# DosTres_v3.net
KiCad netlist of a schematic drawn in EAGLE
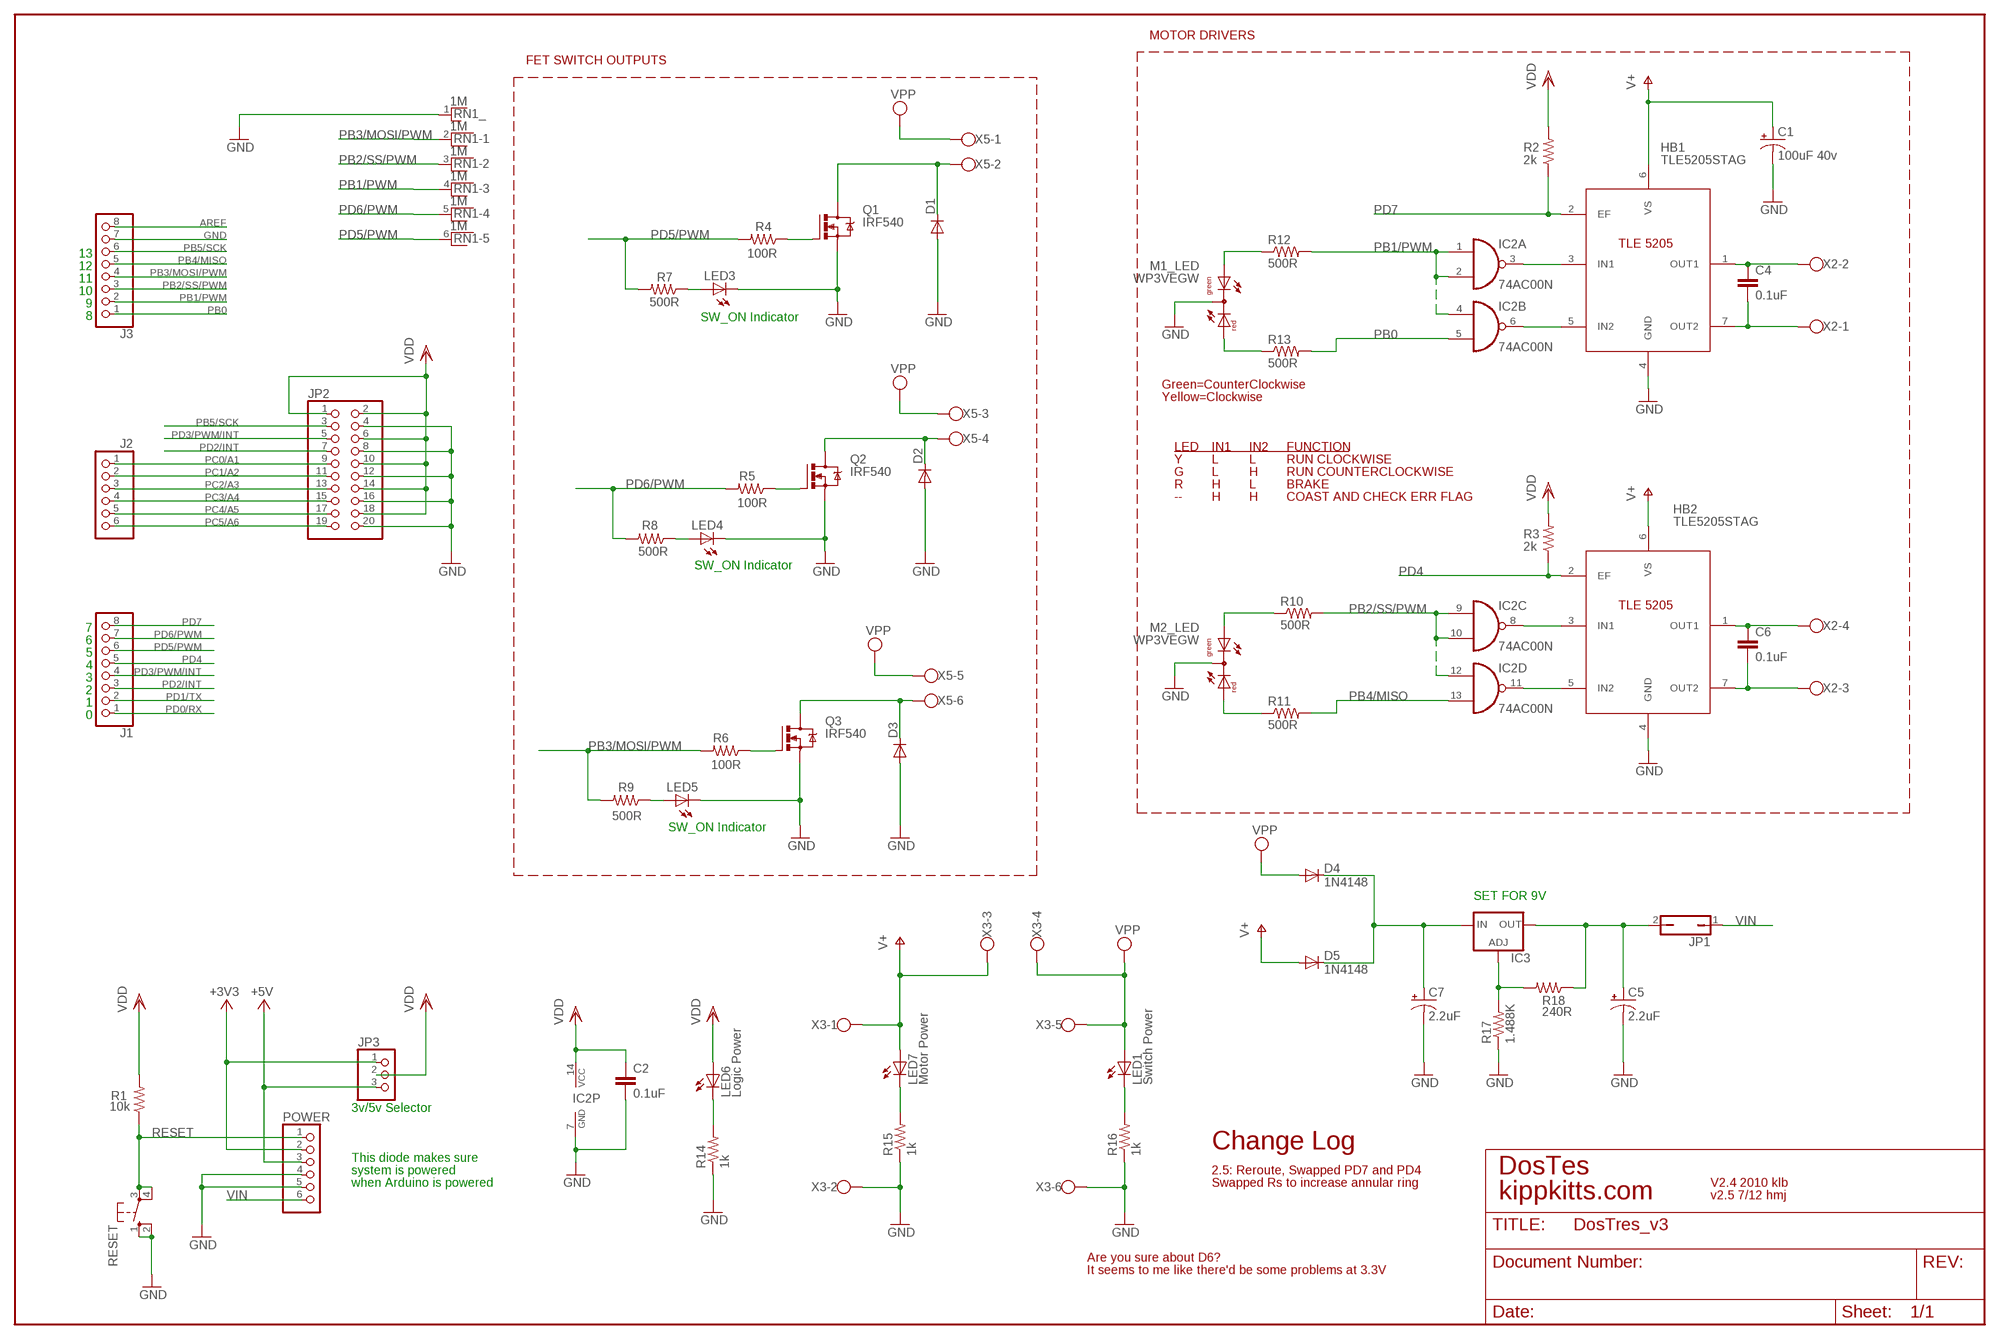
[diagram p0: schematic, sheet 1]

(export (version "E")
  (design (tool "Eeschema 10.0.6"))
  (components
    (comp (ref "C1")
      (value "100uF 40v")
      (footprint "eagle-import:E2,5-6E")
      (libsource (lib "eagle-import") (part "CPOL-USE2,5-6E"))
    )
    (comp (ref "C2")
      (value "0.1uF")
      (footprint "eagle-import:CAP-PTH-SMALL-KIT")
      (libsource (lib "eagle-import") (part "CAPKIT"))
    )
    (comp (ref "C4")
      (value "0.1uF")
      (footprint "eagle-import:CAP-PTH-SMALL-KIT")
      (libsource (lib "eagle-import") (part "CAPKIT"))
    )
    (comp (ref "C5")
      (value "2.2uF")
      (footprint "eagle-import:CPOL-RADIAL-10UF-25V")
      (libsource (lib "eagle-import") (part "CAP_POLPTH2"))
    )
    (comp (ref "C6")
      (value "0.1uF")
      (footprint "eagle-import:CAP-PTH-SMALL-KIT")
      (libsource (lib "eagle-import") (part "CAPKIT"))
    )
    (comp (ref "C7")
      (value "2.2uF")
      (footprint "eagle-import:CPOL-RADIAL-10UF-25V")
      (libsource (lib "eagle-import") (part "CAP_POLPTH2"))
    )
    (comp (ref "D1")
      (value "DIODE-1MMHOLED-7.5BH")
      (footprint "eagle-import:D-7.5BH")
      (libsource (lib "eagle-import") (part "DIODE-1MMHOLED-7.5BH"))
    )
    (comp (ref "D2")
      (value "DIODE-1MMHOLED-7.5BH")
      (footprint "eagle-import:D-7.5BH")
      (libsource (lib "eagle-import") (part "DIODE-1MMHOLED-7.5BH"))
    )
    (comp (ref "D3")
      (value "DIODE-1MMHOLED-7.5BH")
      (footprint "eagle-import:D-7.5BH")
      (libsource (lib "eagle-import") (part "DIODE-1MMHOLED-7.5BH"))
    )
    (comp (ref "D4")
      (value "1N4148")
      (footprint "eagle-import:D-7.5BH")
      (libsource (lib "eagle-import") (part "DIODE-1MMHOLED-7.5BH"))
    )
    (comp (ref "D5")
      (value "1N4148")
      (footprint "eagle-import:D-7.5BH")
      (libsource (lib "eagle-import") (part "DIODE-1MMHOLED-7.5BH"))
    )
    (comp (ref "HB1")
      (value "TLE5205STAG")
      (footprint "eagle-import:TO220-7-11")
      (libsource (lib "eagle-import") (part "TLE5205STAG"))
    )
    (comp (ref "HB2")
      (value "TLE5205STAG")
      (footprint "eagle-import:TO220-7-11")
      (libsource (lib "eagle-import") (part "TLE5205STAG"))
    )
    (comp (ref "IC2")
      (value "74AC00N")
      (footprint "eagle-import:DIL14")
      (libsource (lib "eagle-import") (part "7400NAC"))
    )
    (comp (ref "IC3")
      (value "LM317TS")
      (footprint "eagle-import:317TS")
      (libsource (lib "eagle-import") (part "LM317TS"))
    )
    (comp (ref "J1")
      (value "PINHD-1X8")
      (footprint "eagle-import:1X08")
      (libsource (lib "eagle-import") (part "PINHD-1X8"))
    )
    (comp (ref "J2")
      (value "PINHD-1X6")
      (footprint "eagle-import:1X06")
      (libsource (lib "eagle-import") (part "PINHD-1X6"))
    )
    (comp (ref "J3")
      (value "PINHD-1X8")
      (footprint "eagle-import:1X08")
      (libsource (lib "eagle-import") (part "PINHD-1X8"))
    )
    (comp (ref "JP1")
      (value "JP1Q")
      (footprint "eagle-import:JP1")
      (libsource (lib "eagle-import") (part "JP1Q"))
    )
    (comp (ref "JP2")
      (value "PINHD-2X10HAND")
      (footprint "eagle-import:2X10HAND")
      (libsource (lib "eagle-import") (part "PINHD-2X10HAND"))
    )
    (comp (ref "JP3")
      (value "PINHD-1X3")
      (footprint "eagle-import:1X03")
      (libsource (lib "eagle-import") (part "PINHD-1X3"))
    )
    (comp (ref "LED1")
      (value "Switch Power")
      (footprint "eagle-import:LED3MM")
      (libsource (lib "eagle-import") (part "LED3MMX1MM3MM"))
    )
    (comp (ref "LED3")
      (value "LED3MMX1MM3MM")
      (footprint "eagle-import:LED3MM")
      (libsource (lib "eagle-import") (part "LED3MMX1MM3MM"))
    )
    (comp (ref "LED4")
      (value "LED3MMX1MM3MM")
      (footprint "eagle-import:LED3MM")
      (libsource (lib "eagle-import") (part "LED3MMX1MM3MM"))
    )
    (comp (ref "LED5")
      (value "LED3MMX1MM3MM")
      (footprint "eagle-import:LED3MM")
      (libsource (lib "eagle-import") (part "LED3MMX1MM3MM"))
    )
    (comp (ref "LED6")
      (value "Logic Power")
      (footprint "eagle-import:LED3MM")
      (libsource (lib "eagle-import") (part "LED3MMX1MM3MM"))
    )
    (comp (ref "LED7")
      (value "Motor Power")
      (footprint "eagle-import:LED3MM")
      (libsource (lib "eagle-import") (part "LED3MMX1MM3MM"))
    )
    (comp (ref "M1_LED")
      (value "WP3VEGW")
      (footprint "eagle-import:DUOLED-A-3MM")
      (libsource (lib "eagle-import") (part "WP3VEGW"))
    )
    (comp (ref "M2_LED")
      (value "WP3VEGW")
      (footprint "eagle-import:DUOLED-A-3MM")
      (libsource (lib "eagle-import") (part "WP3VEGW"))
    )
    (comp (ref "POWER")
      (value "PINHD-1X6")
      (footprint "eagle-import:1X06")
      (libsource (lib "eagle-import") (part "PINHD-1X6"))
    )
    (comp (ref "Q1")
      (value "IRF540")
      (footprint "eagle-import:TO220BV")
      (libsource (lib "eagle-import") (part "IRF540"))
    )
    (comp (ref "Q2")
      (value "IRF540")
      (footprint "eagle-import:TO220BV")
      (libsource (lib "eagle-import") (part "IRF540"))
    )
    (comp (ref "Q3")
      (value "IRF540")
      (footprint "eagle-import:TO220BV")
      (libsource (lib "eagle-import") (part "IRF540"))
    )
    (comp (ref "R1")
      (value "10k")
      (footprint "eagle-import:0207_2V")
      (libsource (lib "eagle-import") (part "R-US_0207/2V"))
    )
    (comp (ref "R2")
      (value "2k")
      (footprint "eagle-import:0207_2V")
      (libsource (lib "eagle-import") (part "R-US_0207/2V"))
    )
    (comp (ref "R3")
      (value "2k")
      (footprint "eagle-import:0207_2V")
      (libsource (lib "eagle-import") (part "R-US_0207/2V"))
    )
    (comp (ref "R4")
      (value "100R")
      (footprint "eagle-import:0207_2V")
      (libsource (lib "eagle-import") (part "R-US_0207/2V"))
    )
    (comp (ref "R5")
      (value "100R")
      (footprint "eagle-import:0207_2V")
      (libsource (lib "eagle-import") (part "R-US_0207/2V"))
    )
    (comp (ref "R6")
      (value "100R")
      (footprint "eagle-import:0207_2V")
      (libsource (lib "eagle-import") (part "R-US_0207/2V"))
    )
    (comp (ref "R7")
      (value "500R")
      (footprint "eagle-import:0207_2V")
      (libsource (lib "eagle-import") (part "R-US_0207/2V"))
    )
    (comp (ref "R8")
      (value "500R")
      (footprint "eagle-import:0207_2V")
      (libsource (lib "eagle-import") (part "R-US_0207/2V"))
    )
    (comp (ref "R9")
      (value "500R")
      (footprint "eagle-import:0207_2V")
      (libsource (lib "eagle-import") (part "R-US_0207/2V"))
    )
    (comp (ref "R10")
      (value "500R")
      (footprint "eagle-import:0207_2V")
      (libsource (lib "eagle-import") (part "R-US_0207/2V"))
    )
    (comp (ref "R11")
      (value "500R")
      (footprint "eagle-import:0207_2V")
      (libsource (lib "eagle-import") (part "R-US_0207/2V"))
    )
    (comp (ref "R12")
      (value "500R")
      (footprint "eagle-import:0207_2V")
      (libsource (lib "eagle-import") (part "R-US_0207/2V"))
    )
    (comp (ref "R13")
      (value "500R")
      (footprint "eagle-import:0207_2V")
      (libsource (lib "eagle-import") (part "R-US_0207/2V"))
    )
    (comp (ref "R14")
      (value "1k")
      (footprint "eagle-import:0207_2V")
      (libsource (lib "eagle-import") (part "R-US_0207/2V"))
    )
    (comp (ref "R15")
      (value "1k")
      (footprint "eagle-import:0207_2V")
      (libsource (lib "eagle-import") (part "R-US_0207/2V"))
    )
    (comp (ref "R16")
      (value "1k")
      (footprint "eagle-import:0207_2V")
      (libsource (lib "eagle-import") (part "R-US_0207/2V"))
    )
    (comp (ref "R17")
      (value "1.488K")
      (footprint "eagle-import:0207_2V")
      (libsource (lib "eagle-import") (part "R-US_0207/2V"))
    )
    (comp (ref "R18")
      (value "240R")
      (footprint "eagle-import:0207_2V")
      (libsource (lib "eagle-import") (part "R-US_0207/2V"))
    )
    (comp (ref "RESET")
      (value "10-XX")
      (footprint "eagle-import:B3F-10XX")
      (fields (field (name "MPN") "B3F-1000"))
      (libsource (lib "eagle-import") (part "10-XX"))
    )
    (comp (ref "RN1")
      (value "1M")
      (footprint "eagle-import:RN-6")
      (libsource (lib "eagle-import") (part "RNX5"))
    )
    (comp (ref "X2")
      (value "W237-4")
      (footprint "eagle-import:W237-4")
      (libsource (lib "eagle-import") (part "W237-4"))
    )
    (comp (ref "X3")
      (value "W237-6")
      (footprint "eagle-import:W237-6")
      (libsource (lib "eagle-import") (part "W237-6"))
    )
    (comp (ref "X5")
      (value "W237-6")
      (footprint "eagle-import:W237-6")
      (libsource (lib "eagle-import") (part "W237-6"))
    )
  )
  (nets
    (net (code "1") (name "+3V3") (class "Default")
      (node (ref "JP3") (pin "1") (pinfunction "1_1") (pintype "passive"))
      (node (ref "POWER") (pin "2") (pinfunction "2_2") (pintype "passive"))
    )
    (net (code "2") (name "+5V") (class "Default")
      (node (ref "JP3") (pin "3") (pinfunction "3_3") (pintype "passive"))
      (node (ref "POWER") (pin "3") (pinfunction "3_3") (pintype "passive"))
    )
    (net (code "3") (name "/AREF") (class "Default")
      (node (ref "J3") (pin "8") (pinfunction "8_8") (pintype "passive"))
    )
    (net (code "4") (name "/PB0") (class "Default")
      (node (ref "IC2") (pin "5") (pinfunction "I1_5") (pintype "input"))
      (node (ref "J3") (pin "1") (pinfunction "1_1") (pintype "passive"))
      (node (ref "R13") (pin "2") (pinfunction "2_2") (pintype "passive"))
    )
    (net (code "5") (name "/PB1{slash}PWM") (class "Default")
      (node (ref "IC2") (pin "1") (pinfunction "I0_1") (pintype "input"))
      (node (ref "IC2") (pin "2") (pinfunction "I1_2") (pintype "input"))
      (node (ref "IC2") (pin "4") (pinfunction "I0_4") (pintype "input"))
      (node (ref "J3") (pin "2") (pinfunction "2_2") (pintype "passive"))
      (node (ref "R12") (pin "2") (pinfunction "2_2") (pintype "passive"))
      (node (ref "RN1") (pin "4") (pinfunction "1_4") (pintype "passive"))
    )
    (net (code "6") (name "/PB2{slash}SS{slash}PWM") (class "Default")
      (node (ref "IC2") (pin "10") (pinfunction "I1_10") (pintype "input"))
      (node (ref "IC2") (pin "12") (pinfunction "I0_12") (pintype "input"))
      (node (ref "IC2") (pin "9") (pinfunction "I0_9") (pintype "input"))
      (node (ref "J3") (pin "3") (pinfunction "3_3") (pintype "passive"))
      (node (ref "R10") (pin "2") (pinfunction "2_2") (pintype "passive"))
      (node (ref "RN1") (pin "3") (pinfunction "1_3") (pintype "passive"))
    )
    (net (code "7") (name "/PB3{slash}MOSI{slash}PWM") (class "Default")
      (node (ref "J3") (pin "4") (pinfunction "4_4") (pintype "passive"))
      (node (ref "R6") (pin "2") (pinfunction "2_2") (pintype "passive"))
      (node (ref "R9") (pin "2") (pinfunction "2_2") (pintype "passive"))
      (node (ref "RN1") (pin "2") (pinfunction "1_2") (pintype "passive"))
    )
    (net (code "8") (name "/PB4{slash}MISO") (class "Default")
      (node (ref "IC2") (pin "13") (pinfunction "I1_13") (pintype "input"))
      (node (ref "J3") (pin "5") (pinfunction "5_5") (pintype "passive"))
      (node (ref "R11") (pin "2") (pinfunction "2_2") (pintype "passive"))
    )
    (net (code "9") (name "/PB5{slash}SCK") (class "Default")
      (node (ref "J3") (pin "6") (pinfunction "6_6") (pintype "passive"))
      (node (ref "JP2") (pin "3") (pinfunction "3_3") (pintype "passive"))
    )
    (net (code "10") (name "/PC0{slash}A1") (class "Default")
      (node (ref "J2") (pin "1") (pinfunction "1_1") (pintype "passive"))
      (node (ref "JP2") (pin "9") (pinfunction "9_9") (pintype "passive"))
    )
    (net (code "11") (name "/PC1{slash}A2") (class "Default")
      (node (ref "J2") (pin "2") (pinfunction "2_2") (pintype "passive"))
      (node (ref "JP2") (pin "11") (pinfunction "11_11") (pintype "passive"))
    )
    (net (code "12") (name "/PC2{slash}A3") (class "Default")
      (node (ref "J2") (pin "3") (pinfunction "3_3") (pintype "passive"))
      (node (ref "JP2") (pin "13") (pinfunction "13_13") (pintype "passive"))
    )
    (net (code "13") (name "/PC3{slash}A4") (class "Default")
      (node (ref "J2") (pin "4") (pinfunction "4_4") (pintype "passive"))
      (node (ref "JP2") (pin "15") (pinfunction "15_15") (pintype "passive"))
    )
    (net (code "14") (name "/PC4{slash}A5") (class "Default")
      (node (ref "J2") (pin "5") (pinfunction "5_5") (pintype "passive"))
      (node (ref "JP2") (pin "17") (pinfunction "17_17") (pintype "passive"))
    )
    (net (code "15") (name "/PC5{slash}A6") (class "Default")
      (node (ref "J2") (pin "6") (pinfunction "6_6") (pintype "passive"))
      (node (ref "JP2") (pin "19") (pinfunction "19_19") (pintype "passive"))
    )
    (net (code "16") (name "/PD0{slash}RX") (class "Default")
      (node (ref "J1") (pin "1") (pinfunction "1_1") (pintype "passive"))
    )
    (net (code "17") (name "/PD1{slash}TX") (class "Default")
      (node (ref "J1") (pin "2") (pinfunction "2_2") (pintype "passive"))
    )
    (net (code "18") (name "/PD2{slash}INT") (class "Default")
      (node (ref "J1") (pin "3") (pinfunction "3_3") (pintype "passive"))
      (node (ref "JP2") (pin "7") (pinfunction "7_7") (pintype "passive"))
    )
    (net (code "19") (name "/PD3{slash}PWM{slash}INT") (class "Default")
      (node (ref "J1") (pin "4") (pinfunction "4_4") (pintype "passive"))
      (node (ref "JP2") (pin "5") (pinfunction "5_5") (pintype "passive"))
    )
    (net (code "20") (name "/PD4") (class "Default")
      (node (ref "HB2") (pin "2") (pinfunction "EF_2") (pintype "output"))
      (node (ref "J1") (pin "5") (pinfunction "5_5") (pintype "passive"))
      (node (ref "R3") (pin "1") (pinfunction "1_1") (pintype "passive"))
    )
    (net (code "21") (name "/PD5{slash}PWM") (class "Default")
      (node (ref "J1") (pin "6") (pinfunction "6_6") (pintype "passive"))
      (node (ref "R4") (pin "2") (pinfunction "2_2") (pintype "passive"))
      (node (ref "R7") (pin "2") (pinfunction "2_2") (pintype "passive"))
      (node (ref "RN1") (pin "6") (pinfunction "1_6") (pintype "passive"))
    )
    (net (code "22") (name "/PD6{slash}PWM") (class "Default")
      (node (ref "J1") (pin "7") (pinfunction "7_7") (pintype "passive"))
      (node (ref "R5") (pin "2") (pinfunction "2_2") (pintype "passive"))
      (node (ref "R8") (pin "2") (pinfunction "2_2") (pintype "passive"))
      (node (ref "RN1") (pin "5") (pinfunction "1_5") (pintype "passive"))
    )
    (net (code "23") (name "/PD7") (class "Default")
      (node (ref "HB1") (pin "2") (pinfunction "EF_2") (pintype "output"))
      (node (ref "J1") (pin "8") (pinfunction "8_8") (pintype "passive"))
      (node (ref "R2") (pin "1") (pinfunction "1_1") (pintype "passive"))
    )
    (net (code "24") (name "/RESET") (class "Default")
      (node (ref "POWER") (pin "1") (pinfunction "1_1") (pintype "passive"))
      (node (ref "R1") (pin "1") (pinfunction "1_1") (pintype "passive"))
      (node (ref "RESET") (pin "3") (pinfunction "P_3") (pintype "passive"))
      (node (ref "RESET") (pin "4") (pinfunction "P1_4") (pintype "passive"))
    )
    (net (code "25") (name "/VIN") (class "Default")
      (node (ref "JP1") (pin "1") (pinfunction "1_1") (pintype "passive"))
      (node (ref "POWER") (pin "6") (pinfunction "6_6") (pintype "passive"))
    )
    (net (code "26") (name "GND") (class "Default")
      (node (ref "C1") (pin "-") (pinfunction "-_-") (pintype "passive"))
      (node (ref "C2") (pin "2") (pinfunction "2_2") (pintype "passive"))
      (node (ref "C5") (pin "2") (pinfunction "-_2") (pintype "passive"))
      (node (ref "C7") (pin "2") (pinfunction "-_2") (pintype "passive"))
      (node (ref "D1") (pin "A") (pinfunction "A_A") (pintype "passive"))
      (node (ref "D2") (pin "A") (pinfunction "A_A") (pintype "passive"))
      (node (ref "D3") (pin "A") (pinfunction "A_A") (pintype "passive"))
      (node (ref "HB1") (pin "4") (pinfunction "GND_4") (pintype "power_in"))
      (node (ref "HB2") (pin "4") (pinfunction "GND_4") (pintype "power_in"))
      (node (ref "IC2") (pin "7") (pinfunction "GND_7") (pintype "power_in"))
      (node (ref "J3") (pin "7") (pinfunction "7_7") (pintype "passive"))
      (node (ref "JP2") (pin "12") (pinfunction "12_12") (pintype "passive"))
      (node (ref "JP2") (pin "16") (pinfunction "16_16") (pintype "passive"))
      (node (ref "JP2") (pin "20") (pinfunction "20_20") (pintype "passive"))
      (node (ref "JP2") (pin "4") (pinfunction "4_4") (pintype "passive"))
      (node (ref "JP2") (pin "8") (pinfunction "8_8") (pintype "passive"))
      (node (ref "LED3") (pin "K") (pinfunction "C_K") (pintype "passive"))
      (node (ref "LED4") (pin "K") (pinfunction "C_K") (pintype "passive"))
      (node (ref "LED5") (pin "K") (pinfunction "C_K") (pintype "passive"))
      (node (ref "M1_LED") (pin "2") (pinfunction "C_2") (pintype "passive"))
      (node (ref "M2_LED") (pin "2") (pinfunction "C_2") (pintype "passive"))
      (node (ref "POWER") (pin "4") (pinfunction "4_4") (pintype "passive"))
      (node (ref "POWER") (pin "5") (pinfunction "5_5") (pintype "passive"))
      (node (ref "Q1") (pin "S") (pinfunction "S_S") (pintype "passive"))
      (node (ref "Q2") (pin "S") (pinfunction "S_S") (pintype "passive"))
      (node (ref "Q3") (pin "S") (pinfunction "S_S") (pintype "passive"))
      (node (ref "R14") (pin "1") (pinfunction "1_1") (pintype "passive"))
      (node (ref "R15") (pin "1") (pinfunction "1_1") (pintype "passive"))
      (node (ref "R16") (pin "1") (pinfunction "1_1") (pintype "passive"))
      (node (ref "R17") (pin "1") (pinfunction "1_1") (pintype "passive"))
      (node (ref "RESET") (pin "1") (pinfunction "S_1") (pintype "passive"))
      (node (ref "RESET") (pin "2") (pinfunction "S1_2") (pintype "passive"))
      (node (ref "RN1") (pin "1") (pinfunction "1_1") (pintype "passive"))
      (node (ref "X3") (pin "2") (pinfunction "KL_2") (pintype "passive"))
      (node (ref "X3") (pin "6") (pinfunction "KL_6") (pintype "passive"))
    )
    (net (code "27") (name "Net-(C5-+)") (class "Default")
      (node (ref "C5") (pin "1") (pinfunction "+_1") (pintype "passive"))
      (node (ref "IC3") (pin "2") (pinfunction "OUT_2") (pintype "passive"))
      (node (ref "JP1") (pin "2") (pinfunction "2_2") (pintype "passive"))
      (node (ref "R18") (pin "1") (pinfunction "1_1") (pintype "passive"))
    )
    (net (code "28") (name "Net-(C7-+)") (class "Default")
      (node (ref "C7") (pin "1") (pinfunction "+_1") (pintype "passive"))
      (node (ref "D4") (pin "C") (pinfunction "C_C") (pintype "passive"))
      (node (ref "D5") (pin "C") (pinfunction "C_C") (pintype "passive"))
      (node (ref "IC3") (pin "3") (pinfunction "IN_3") (pintype "input"))
    )
    (net (code "29") (name "Net-(HB1-IN1)") (class "Default")
      (node (ref "HB1") (pin "3") (pinfunction "IN1_3") (pintype "input"))
      (node (ref "IC2") (pin "3") (pinfunction "O_3") (pintype "output"))
    )
    (net (code "30") (name "Net-(HB1-IN2)") (class "Default")
      (node (ref "HB1") (pin "5") (pinfunction "IN2_5") (pintype "input"))
      (node (ref "IC2") (pin "6") (pinfunction "O_6") (pintype "output"))
    )
    (net (code "31") (name "Net-(HB1-OUT1)") (class "Default")
      (node (ref "C4") (pin "1") (pinfunction "1_1") (pintype "passive"))
      (node (ref "HB1") (pin "1") (pinfunction "OUT1_1") (pintype "output"))
      (node (ref "X2") (pin "2") (pinfunction "KL_2") (pintype "passive"))
    )
    (net (code "32") (name "Net-(HB1-OUT2)") (class "Default")
      (node (ref "C4") (pin "2") (pinfunction "2_2") (pintype "passive"))
      (node (ref "HB1") (pin "7") (pinfunction "OUT2_7") (pintype "output"))
      (node (ref "X2") (pin "1") (pinfunction "KL_1") (pintype "passive"))
    )
    (net (code "33") (name "Net-(HB2-IN1)") (class "Default")
      (node (ref "HB2") (pin "3") (pinfunction "IN1_3") (pintype "input"))
      (node (ref "IC2") (pin "8") (pinfunction "O_8") (pintype "output"))
    )
    (net (code "34") (name "Net-(HB2-IN2)") (class "Default")
      (node (ref "HB2") (pin "5") (pinfunction "IN2_5") (pintype "input"))
      (node (ref "IC2") (pin "11") (pinfunction "O_11") (pintype "output"))
    )
    (net (code "35") (name "Net-(HB2-OUT1)") (class "Default")
      (node (ref "C6") (pin "1") (pinfunction "1_1") (pintype "passive"))
      (node (ref "HB2") (pin "1") (pinfunction "OUT1_1") (pintype "output"))
      (node (ref "X2") (pin "4") (pinfunction "KL_4") (pintype "passive"))
    )
    (net (code "36") (name "Net-(HB2-OUT2)") (class "Default")
      (node (ref "C6") (pin "2") (pinfunction "2_2") (pintype "passive"))
      (node (ref "HB2") (pin "7") (pinfunction "OUT2_7") (pintype "output"))
      (node (ref "X2") (pin "3") (pinfunction "KL_3") (pintype "passive"))
    )
    (net (code "37") (name "Net-(IC3-ADJ)") (class "Default")
      (node (ref "IC3") (pin "1") (pinfunction "ADJ_1") (pintype "input"))
      (node (ref "R17") (pin "2") (pinfunction "2_2") (pintype "passive"))
      (node (ref "R18") (pin "2") (pinfunction "2_2") (pintype "passive"))
    )
    (net (code "38") (name "Net-(LED1-C)") (class "Default")
      (node (ref "LED1") (pin "K") (pinfunction "C_K") (pintype "passive"))
      (node (ref "R16") (pin "2") (pinfunction "2_2") (pintype "passive"))
    )
    (net (code "39") (name "Net-(LED3-PadA)") (class "Default")
      (node (ref "LED3") (pin "A") (pinfunction "A_A") (pintype "passive"))
      (node (ref "R7") (pin "1") (pinfunction "1_1") (pintype "passive"))
    )
    (net (code "40") (name "Net-(LED4-PadA)") (class "Default")
      (node (ref "LED4") (pin "A") (pinfunction "A_A") (pintype "passive"))
      (node (ref "R8") (pin "1") (pinfunction "1_1") (pintype "passive"))
    )
    (net (code "41") (name "Net-(LED5-PadA)") (class "Default")
      (node (ref "LED5") (pin "A") (pinfunction "A_A") (pintype "passive"))
      (node (ref "R9") (pin "1") (pinfunction "1_1") (pintype "passive"))
    )
    (net (code "42") (name "Net-(LED6-C)") (class "Default")
      (node (ref "LED6") (pin "K") (pinfunction "C_K") (pintype "passive"))
      (node (ref "R14") (pin "2") (pinfunction "2_2") (pintype "passive"))
    )
    (net (code "43") (name "Net-(LED7-C)") (class "Default")
      (node (ref "LED7") (pin "K") (pinfunction "C_K") (pintype "passive"))
      (node (ref "R15") (pin "2") (pinfunction "2_2") (pintype "passive"))
    )
    (net (code "44") (name "Net-(M1_LED-AG)") (class "Default")
      (node (ref "M1_LED") (pin "3") (pinfunction "AG_3") (pintype "passive"))
      (node (ref "R12") (pin "1") (pinfunction "1_1") (pintype "passive"))
    )
    (net (code "45") (name "Net-(M1_LED-AR)") (class "Default")
      (node (ref "M1_LED") (pin "1") (pinfunction "AR_1") (pintype "passive"))
      (node (ref "R13") (pin "1") (pinfunction "1_1") (pintype "passive"))
    )
    (net (code "46") (name "Net-(M2_LED-AG)") (class "Default")
      (node (ref "M2_LED") (pin "3") (pinfunction "AG_3") (pintype "passive"))
      (node (ref "R10") (pin "1") (pinfunction "1_1") (pintype "passive"))
    )
    (net (code "47") (name "Net-(M2_LED-AR)") (class "Default")
      (node (ref "M2_LED") (pin "1") (pinfunction "AR_1") (pintype "passive"))
      (node (ref "R11") (pin "1") (pinfunction "1_1") (pintype "passive"))
    )
    (net (code "48") (name "Net-(Q1-PadG)") (class "Default")
      (node (ref "Q1") (pin "G") (pinfunction "G_G") (pintype "passive"))
      (node (ref "R4") (pin "1") (pinfunction "1_1") (pintype "passive"))
    )
    (net (code "49") (name "Net-(Q2-PadG)") (class "Default")
      (node (ref "Q2") (pin "G") (pinfunction "G_G") (pintype "passive"))
      (node (ref "R5") (pin "1") (pinfunction "1_1") (pintype "passive"))
    )
    (net (code "50") (name "Net-(Q3-PadG)") (class "Default")
      (node (ref "Q3") (pin "G") (pinfunction "G_G") (pintype "passive"))
      (node (ref "R6") (pin "1") (pinfunction "1_1") (pintype "passive"))
    )
    (net (code "51") (name "Net-(X5B-KL)") (class "Default")
      (node (ref "D1") (pin "C") (pinfunction "C_C") (pintype "passive"))
      (node (ref "Q1") (pin "D") (pinfunction "D_D") (pintype "passive"))
      (node (ref "X5") (pin "2") (pinfunction "KL_2") (pintype "passive"))
    )
    (net (code "52") (name "Net-(X5D-KL)") (class "Default")
      (node (ref "D2") (pin "C") (pinfunction "C_C") (pintype "passive"))
      (node (ref "Q2") (pin "D") (pinfunction "D_D") (pintype "passive"))
      (node (ref "X5") (pin "4") (pinfunction "KL_4") (pintype "passive"))
    )
    (net (code "53") (name "Net-(X5F-KL)") (class "Default")
      (node (ref "D3") (pin "C") (pinfunction "C_C") (pintype "passive"))
      (node (ref "Q3") (pin "D") (pinfunction "D_D") (pintype "passive"))
      (node (ref "X5") (pin "6") (pinfunction "KL_6") (pintype "passive"))
    )
    (net (code "54") (name "V+") (class "Default")
      (node (ref "C1") (pin "+") (pinfunction "+_+") (pintype "passive"))
      (node (ref "D5") (pin "A") (pinfunction "A_A") (pintype "passive"))
      (node (ref "HB1") (pin "6") (pinfunction "VS_6") (pintype "power_in"))
      (node (ref "HB2") (pin "6") (pinfunction "VS_6") (pintype "power_in"))
      (node (ref "LED7") (pin "A") (pinfunction "A_A") (pintype "passive"))
      (node (ref "X3") (pin "1") (pinfunction "KL_1") (pintype "passive"))
      (node (ref "X3") (pin "3") (pinfunction "KL_3") (pintype "passive"))
    )
    (net (code "55") (name "VDD") (class "Default")
      (node (ref "C2") (pin "1") (pinfunction "1_1") (pintype "passive"))
      (node (ref "IC2") (pin "14") (pinfunction "VCC_14") (pintype "power_in"))
      (node (ref "JP2") (pin "1") (pinfunction "1_1") (pintype "passive"))
      (node (ref "JP2") (pin "10") (pinfunction "10_10") (pintype "passive"))
      (node (ref "JP2") (pin "14") (pinfunction "14_14") (pintype "passive"))
      (node (ref "JP2") (pin "18") (pinfunction "18_18") (pintype "passive"))
      (node (ref "JP2") (pin "2") (pinfunction "2_2") (pintype "passive"))
      (node (ref "JP2") (pin "6") (pinfunction "6_6") (pintype "passive"))
      (node (ref "JP3") (pin "2") (pinfunction "2_2") (pintype "passive"))
      (node (ref "LED6") (pin "A") (pinfunction "A_A") (pintype "passive"))
      (node (ref "R1") (pin "2") (pinfunction "2_2") (pintype "passive"))
      (node (ref "R2") (pin "2") (pinfunction "2_2") (pintype "passive"))
      (node (ref "R3") (pin "2") (pinfunction "2_2") (pintype "passive"))
    )
    (net (code "56") (name "VPP") (class "Default")
      (node (ref "D4") (pin "A") (pinfunction "A_A") (pintype "passive"))
      (node (ref "LED1") (pin "A") (pinfunction "A_A") (pintype "passive"))
      (node (ref "X3") (pin "4") (pinfunction "KL_4") (pintype "passive"))
      (node (ref "X3") (pin "5") (pinfunction "KL_5") (pintype "passive"))
      (node (ref "X5") (pin "1") (pinfunction "KL_1") (pintype "passive"))
      (node (ref "X5") (pin "3") (pinfunction "KL_3") (pintype "passive"))
      (node (ref "X5") (pin "5") (pinfunction "KL_5") (pintype "passive"))
    )
  )
)
